# LED_Flasher.net
KiCad netlist of a schematic drawn in EAGLE
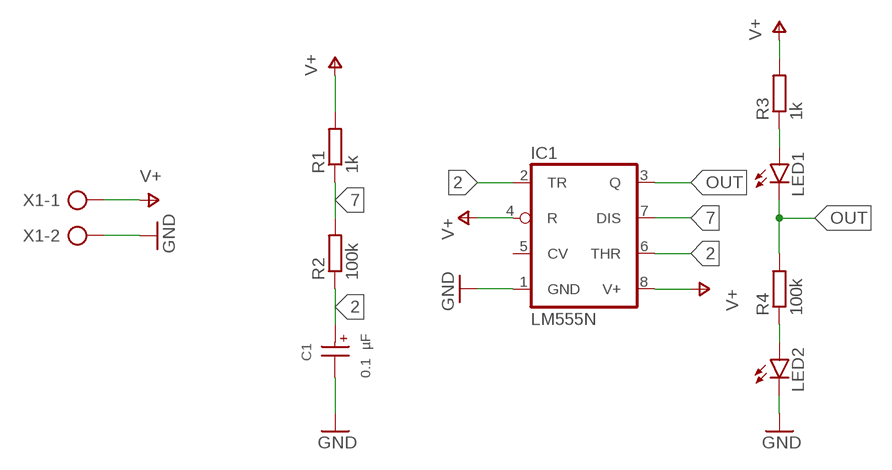
[diagram p0: schematic, sheet 1]

(export (version "E")
  (design (tool "Eeschema 10.0.6"))
  (components
    (comp (ref "C1")
      (value "0.1 µF")
      (footprint "eagle-import:WCAP-ATG8_5X11(DXL)")
      (libsource (lib "eagle-import") (part "WCAP-ATG8_5X11_860010772001"))
    )
    (comp (ref "IC1")
      (value "LM555N")
      (footprint "eagle-import:DIL08")
      (libsource (lib "eagle-import") (part "555NLM"))
    )
    (comp (ref "LED1")
      (value "LED3MM")
      (footprint "eagle-import:LED3MM")
      (libsource (lib "eagle-import") (part "LED3MM"))
    )
    (comp (ref "LED2")
      (value "LED3MM")
      (footprint "eagle-import:LED3MM")
      (libsource (lib "eagle-import") (part "LED3MM"))
    )
    (comp (ref "R1")
      (value "1k")
      (footprint "eagle-import:0204_7")
      (libsource (lib "eagle-import") (part "R-EU_0204/7"))
    )
    (comp (ref "R2")
      (value "100k")
      (footprint "eagle-import:0204_7")
      (libsource (lib "eagle-import") (part "R-EU_0204/7"))
    )
    (comp (ref "R3")
      (value "1k")
      (footprint "eagle-import:0204_7")
      (libsource (lib "eagle-import") (part "R-EU_0204/7"))
    )
    (comp (ref "R4")
      (value "100k")
      (footprint "eagle-import:0204_7")
      (libsource (lib "eagle-import") (part "R-EU_0204/7"))
    )
    (comp (ref "X1")
      (value "AK300/2")
      (footprint "eagle-import:AK300_2")
      (libsource (lib "eagle-import") (part "AK300/2"))
    )
  )
  (nets
    (net (code "1") (name "2") (class "Default")
      (node (ref "C1") (pin "1") (pinfunction "+_1") (pintype "passive"))
      (node (ref "IC1") (pin "2") (pinfunction "TR_2") (pintype "input"))
      (node (ref "IC1") (pin "6") (pinfunction "THR_6") (pintype "input"))
      (node (ref "R2") (pin "1") (pinfunction "1_1") (pintype "passive"))
    )
    (net (code "2") (name "7") (class "Default")
      (node (ref "IC1") (pin "7") (pinfunction "DIS_7") (pintype "input"))
      (node (ref "R1") (pin "1") (pinfunction "1_1") (pintype "passive"))
      (node (ref "R2") (pin "2") (pinfunction "2_2") (pintype "passive"))
    )
    (net (code "3") (name "GND") (class "Default")
      (node (ref "C1") (pin "2") (pinfunction "-_2") (pintype "passive"))
      (node (ref "IC1") (pin "1") (pinfunction "GND_1") (pintype "power_in"))
      (node (ref "LED2") (pin "K") (pinfunction "C_K") (pintype "passive"))
      (node (ref "X1") (pin "2") (pinfunction "KL_2") (pintype "passive"))
    )
    (net (code "4") (name "Net-(LED1-PadA)") (class "Default")
      (node (ref "LED1") (pin "A") (pinfunction "A_A") (pintype "passive"))
      (node (ref "R3") (pin "1") (pinfunction "1_1") (pintype "passive"))
    )
    (net (code "5") (name "Net-(LED2-PadA)") (class "Default")
      (node (ref "LED2") (pin "A") (pinfunction "A_A") (pintype "passive"))
      (node (ref "R4") (pin "1") (pinfunction "1_1") (pintype "passive"))
    )
    (net (code "6") (name "OUT") (class "Default")
      (node (ref "IC1") (pin "3") (pinfunction "Q_3") (pintype "output"))
      (node (ref "LED1") (pin "K") (pinfunction "C_K") (pintype "passive"))
      (node (ref "R4") (pin "2") (pinfunction "2_2") (pintype "passive"))
    )
    (net (code "7") (name "V+") (class "Default")
      (node (ref "IC1") (pin "4") (pinfunction "R_4") (pintype "input"))
      (node (ref "IC1") (pin "8") (pinfunction "V+_8") (pintype "power_in"))
      (node (ref "R1") (pin "2") (pinfunction "2_2") (pintype "passive"))
      (node (ref "R3") (pin "2") (pinfunction "2_2") (pintype "passive"))
      (node (ref "X1") (pin "1") (pinfunction "KL_1") (pintype "passive"))
    )
    (net (code "8") (name "unconnected-(IC1-CV-Pad5)") (class "Default")
      (node (ref "IC1") (pin "5") (pinfunction "CV_5") (pintype "input"))
    )
  )
)
